# N-CW7_UserInterface.net
KiCad netlist of a schematic drawn in Altium Designer
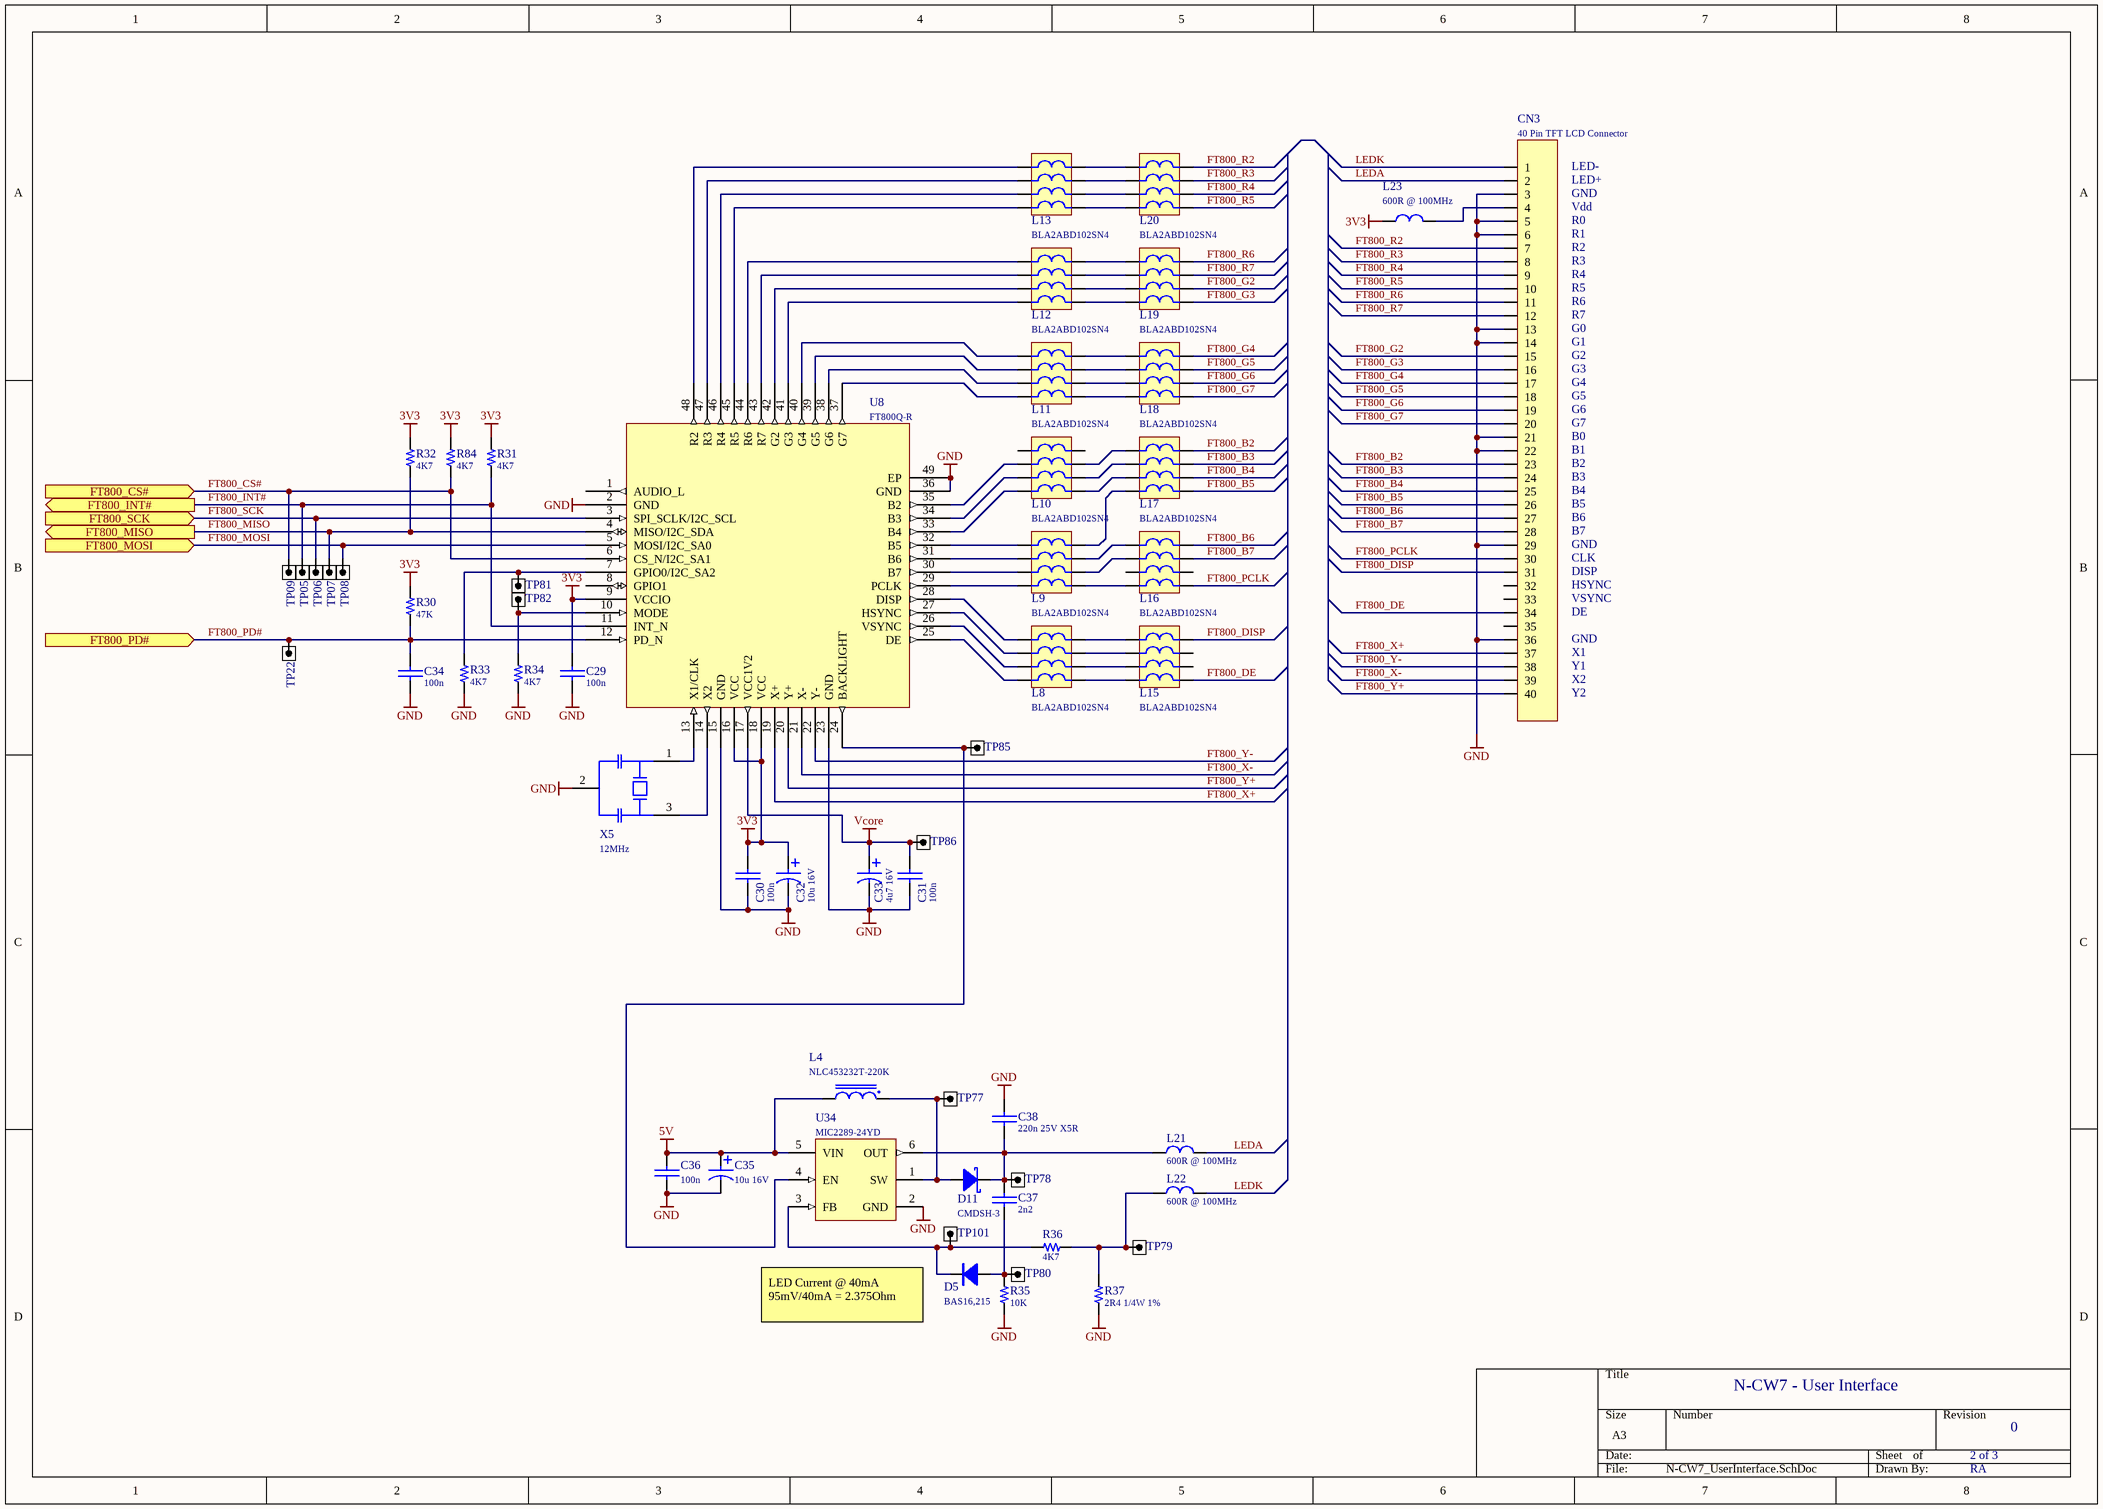
[diagram p0: N-CW7_UserInterface.SchDoc]

(export (version "E")
  (design (tool "Eeschema 10.0.6"))
  (components
    (comp (ref "C29")
      (value "100n")
      (footprint "TDK_0603_T0.80:CAPC1608X08N")
      (description "CAP CER 0.1UF 50V X7R 0603")
      (fields
        (field (name "MANUFACTURER") "TDK")
        (field (name "MANUFACTURER PART NUMBER") "C1608X7R1H104K080AA")
      )
      (libsource (lib "PassiveComponents_Capacitors_Ceramic") (part "TDK_0603_T0.80"))
    )
    (comp (ref "C30")
      (value "100n")
      (footprint "TDK_0603_T0.80:CAPC1608X08N")
      (description "CAP CER 0.1UF 50V X7R 0603")
      (fields
        (field (name "MANUFACTURER") "TDK")
        (field (name "MANUFACTURER PART NUMBER") "C1608X7R1H104K080AA")
      )
      (libsource (lib "PassiveComponents_Capacitors_Ceramic") (part "TDK_0603_T0.80"))
    )
    (comp (ref "C31")
      (value "100n")
      (footprint "TDK_0603_T0.80:CAPC1608X08N")
      (description "CAP CER 0.1UF 50V X7R 0603")
      (fields
        (field (name "MANUFACTURER") "TDK")
        (field (name "MANUFACTURER PART NUMBER") "C1608X7R1H104K080AA")
      )
      (libsource (lib "PassiveComponents_Capacitors_Ceramic") (part "TDK_0603_T0.80"))
    )
    (comp (ref "C32")
      (value "10u 16V")
      (footprint "KEMET_T494B/3528-21:CAPMP3528X19N")
      (description "CAP TANT 10UF 10% 16V 1411")
      (fields
        (field (name "MANUFACTURER") "KEMET")
        (field (name "MANUFACTURER PART NUMBER") "T494B106K016AT")
      )
      (libsource (lib "PassiveComponents_Capacitors_Tantalum") (part "KEMET_T494B/EIA3528-21"))
    )
    (comp (ref "C33")
      (value "4u7 16V")
      (footprint "KEMET_T494A/3216-18:CAPCP3216X16N")
      (description "CAP TANT 4.7UF 10% 16V 1206")
      (fields
        (field (name "MANUFACTURER") "KEMET")
        (field (name "MANUFACTURER PART NUMBER") "T494A475K016AT")
      )
      (libsource (lib "PassiveComponents_Capacitors_Tantalum") (part "KEMET_T494A/EIA3216-18"))
    )
    (comp (ref "C34")
      (value "100n")
      (footprint "TDK_0603_T0.80:CAPC1608X08N")
      (description "CAP CER 0.1UF 50V X7R 0603")
      (fields
        (field (name "MANUFACTURER") "TDK")
        (field (name "MANUFACTURER PART NUMBER") "C1608X7R1H104K080AA")
      )
      (libsource (lib "PassiveComponents_Capacitors_Ceramic") (part "TDK_0603_T0.80"))
    )
    (comp (ref "C35")
      (value "10u 16V")
      (footprint "KEMET_T494B/3528-21:CAPMP3528X19N")
      (description "CAP TANT 10UF 10% 16V 1411")
      (fields
        (field (name "MANUFACTURER") "KEMET")
        (field (name "MANUFACTURER PART NUMBER") "T494B106K016AT")
      )
      (libsource (lib "PassiveComponents_Capacitors_Tantalum") (part "KEMET_T494B/EIA3528-21"))
    )
    (comp (ref "C36")
      (value "100n")
      (footprint "TDK_0603_T0.80:CAPC1608X08N")
      (description "CAP CER 0.1UF 50V X7R 0603")
      (fields
        (field (name "MANUFACTURER") "TDK")
        (field (name "MANUFACTURER PART NUMBER") "C1608X7R1H104K080AA")
      )
      (libsource (lib "PassiveComponents_Capacitors_Ceramic") (part "TDK_0603_T0.80"))
    )
    (comp (ref "C37")
      (value "2n2")
      (footprint "TDK_0603_T0.80:CAPC1608X08N")
      (description "CAP CER 2200PF 50V X7R 0603")
      (fields
        (field (name "MANUFACTURER") "TDK")
        (field (name "MANUFACTURER PART NUMBER") "C1608X7R1H222K080AE")
      )
      (libsource (lib "PassiveComponents_Capacitors_Ceramic") (part "TDK_0603_T0.80"))
    )
    (comp (ref "C38")
      (value "220n 25V X5R")
      (footprint "AVX_0805_T1.40:CAPC2012X14N")
      (description "CAP CER 220n 25V X5R 0805")
      (libsource (lib "PassiveComponents_Capacitors_Ceramic") (part "AVX_0805_T1.40"))
    )
    (comp (ref "CN3")
      (value "40 Pin TFT LCD Connector")
      (footprint "FCI_62684-402100ALF")
      (description "CONN FPC TOP 40POS 0.5MM R/A")
      (fields
        (field (name "MANUFACTURER") "Amphenol ICC / FCI")
        (field (name "MANUFACTURER PART NUMBER") "62684-402100ALF")
      )
      (libsource (lib "Connectors") (part "FCI_62684-402100ALF"))
    )
    (comp (ref "D5")
      (value "BAS16,215")
      (footprint "NEXPERIA_BAS16,215_SOT_23:SOT95P230X110-3N")
      (description "DIODE GP 100V 215MA SOT23")
      (fields (field (name "MANUFACTURER") "Nexperia"))
      (libsource (lib "DiscreteSemiconductors_Diodes_Rectifier") (part "NEXPERIA_BAS16,215_SOT23"))
    )
    (comp (ref "D11")
      (value "CMDSH-3")
      (footprint "CSEMI_CMDSH-3_SOD323")
      (description "DIODE SCHOTTKY 30V 100MA SOD323")
      (fields
        (field (name "MANUFACTURER") "Central Semiconductor")
        (field (name "MANUFACTURER PART NUMBER") "CMDSH-3 TR PBFREE")
      )
      (libsource (lib "DiscreteSemiconductors_Diodes_Rectifier") (part "CSEMI_CMDSH-3_SOD323"))
    )
    (comp (ref "L4")
      (value "NLC453232T-220K")
      (footprint "TDK_NLC453232T-220K")
      (description "22uH 10%")
      (fields
        (field (name "MANUFACTURER") "TDK")
        (field (name "MANUFACTURER PART NUMBER") "NLC453232T-220K-PF")
      )
      (libsource (lib "PassiveComponents_Inductors") (part "TDK_NLC453232T-220K"))
    )
    (comp (ref "L8")
      (value "BLA2ABD102SN4")
      (footprint "MURATA_BLA2ABD102SN4_0804:CAF-50P200X100-8N")
      (description "Ferrite Beads 1000 OHM 25%")
      (fields
        (field (name "MANUFACTURER") "Murata")
        (field (name "MANUFACTURER PART NUMBER") "BLA2ABD102SN4B")
      )
      (libsource (lib "PassiveComponents_Inductors") (part "MURATA_BLA2ABD102SN4_0804"))
    )
    (comp (ref "L9")
      (value "BLA2ABD102SN4")
      (footprint "MURATA_BLA2ABD102SN4_0804:CAF-50P200X100-8N")
      (description "Ferrite Beads 1000 OHM 25%")
      (fields
        (field (name "MANUFACTURER") "Murata")
        (field (name "MANUFACTURER PART NUMBER") "BLA2ABD102SN4B")
      )
      (libsource (lib "PassiveComponents_Inductors") (part "MURATA_BLA2ABD102SN4_0804"))
    )
    (comp (ref "L10")
      (value "BLA2ABD102SN4")
      (footprint "MURATA_BLA2ABD102SN4_0804:CAF-50P200X100-8N")
      (description "Ferrite Beads 1000 OHM 25%")
      (fields
        (field (name "MANUFACTURER") "Murata")
        (field (name "MANUFACTURER PART NUMBER") "BLA2ABD102SN4B")
      )
      (libsource (lib "PassiveComponents_Inductors") (part "MURATA_BLA2ABD102SN4_0804"))
    )
    (comp (ref "L11")
      (value "BLA2ABD102SN4")
      (footprint "MURATA_BLA2ABD102SN4_0804:CAF-50P200X100-8N")
      (description "Ferrite Beads 1000 OHM 25%")
      (fields
        (field (name "MANUFACTURER") "Murata")
        (field (name "MANUFACTURER PART NUMBER") "BLA2ABD102SN4B")
      )
      (libsource (lib "PassiveComponents_Inductors") (part "MURATA_BLA2ABD102SN4_0804"))
    )
    (comp (ref "L12")
      (value "BLA2ABD102SN4")
      (footprint "MURATA_BLA2ABD102SN4_0804:CAF-50P200X100-8N")
      (description "Ferrite Beads 1000 OHM 25%")
      (fields
        (field (name "MANUFACTURER") "Murata")
        (field (name "MANUFACTURER PART NUMBER") "BLA2ABD102SN4B")
      )
      (libsource (lib "PassiveComponents_Inductors") (part "MURATA_BLA2ABD102SN4_0804"))
    )
    (comp (ref "L13")
      (value "BLA2ABD102SN4")
      (footprint "MURATA_BLA2ABD102SN4_0804:CAF-50P200X100-8N")
      (description "Ferrite Beads 1000 OHM 25%")
      (fields
        (field (name "MANUFACTURER") "Murata")
        (field (name "MANUFACTURER PART NUMBER") "BLA2ABD102SN4B")
      )
      (libsource (lib "PassiveComponents_Inductors") (part "MURATA_BLA2ABD102SN4_0804"))
    )
    (comp (ref "L15")
      (value "BLA2ABD102SN4")
      (footprint "MURATA_BLA2ABD102SN4_0804:CAF-50P200X100-8N")
      (description "Ferrite Beads 1000 OHM 25%")
      (fields
        (field (name "MANUFACTURER") "Murata")
        (field (name "MANUFACTURER PART NUMBER") "BLA2ABD102SN4B")
      )
      (libsource (lib "PassiveComponents_Inductors") (part "MURATA_BLA2ABD102SN4_0804"))
    )
    (comp (ref "L16")
      (value "BLA2ABD102SN4")
      (footprint "MURATA_BLA2ABD102SN4_0804:CAF-50P200X100-8N")
      (description "Ferrite Beads 1000 OHM 25%")
      (fields
        (field (name "MANUFACTURER") "Murata")
        (field (name "MANUFACTURER PART NUMBER") "BLA2ABD102SN4B")
      )
      (libsource (lib "PassiveComponents_Inductors") (part "MURATA_BLA2ABD102SN4_0804"))
    )
    (comp (ref "L17")
      (value "BLA2ABD102SN4")
      (footprint "MURATA_BLA2ABD102SN4_0804:CAF-50P200X100-8N")
      (description "Ferrite Beads 1000 OHM 25%")
      (fields
        (field (name "MANUFACTURER") "Murata")
        (field (name "MANUFACTURER PART NUMBER") "BLA2ABD102SN4B")
      )
      (libsource (lib "PassiveComponents_Inductors") (part "MURATA_BLA2ABD102SN4_0804"))
    )
    (comp (ref "L18")
      (value "BLA2ABD102SN4")
      (footprint "MURATA_BLA2ABD102SN4_0804:CAF-50P200X100-8N")
      (description "Ferrite Beads 1000 OHM 25%")
      (fields
        (field (name "MANUFACTURER") "Murata")
        (field (name "MANUFACTURER PART NUMBER") "BLA2ABD102SN4B")
      )
      (libsource (lib "PassiveComponents_Inductors") (part "MURATA_BLA2ABD102SN4_0804"))
    )
    (comp (ref "L19")
      (value "BLA2ABD102SN4")
      (footprint "MURATA_BLA2ABD102SN4_0804:CAF-50P200X100-8N")
      (description "Ferrite Beads 1000 OHM 25%")
      (fields
        (field (name "MANUFACTURER") "Murata")
        (field (name "MANUFACTURER PART NUMBER") "BLA2ABD102SN4B")
      )
      (libsource (lib "PassiveComponents_Inductors") (part "MURATA_BLA2ABD102SN4_0804"))
    )
    (comp (ref "L20")
      (value "BLA2ABD102SN4")
      (footprint "MURATA_BLA2ABD102SN4_0804:CAF-50P200X100-8N")
      (description "Ferrite Beads 1000 OHM 25%")
      (fields
        (field (name "MANUFACTURER") "Murata")
        (field (name "MANUFACTURER PART NUMBER") "BLA2ABD102SN4B")
      )
      (libsource (lib "PassiveComponents_Inductors") (part "MURATA_BLA2ABD102SN4_0804"))
    )
    (comp (ref "L21")
      (value "600R @ 100MHz")
      (footprint "LAIRD_MI0805K601R-10:INDC2012X09N")
      (description "FERRITE BEAD 600 OHM 0805 1LN")
      (fields
        (field (name "MANUFACTURER") "Laird")
        (field (name "MANUFACTURER PART NUMBER") "MI0805K601R-10")
      )
      (libsource (lib "PassiveComponents_Inductors") (part "LAIRD_MI0805K601R-10"))
    )
    (comp (ref "L22")
      (value "600R @ 100MHz")
      (footprint "LAIRD_MI0805K601R-10:INDC2012X09N")
      (description "FERRITE BEAD 600 OHM 0805 1LN")
      (fields
        (field (name "MANUFACTURER") "Laird")
        (field (name "MANUFACTURER PART NUMBER") "MI0805K601R-10")
      )
      (libsource (lib "PassiveComponents_Inductors") (part "LAIRD_MI0805K601R-10"))
    )
    (comp (ref "L23")
      (value "600R @ 100MHz")
      (footprint "LAIRD_MI0805K601R-10:INDC2012X09N")
      (description "FERRITE BEAD 600 OHM 0805 1LN")
      (fields
        (field (name "MANUFACTURER") "Laird")
        (field (name "MANUFACTURER PART NUMBER") "MI0805K601R-10")
      )
      (libsource (lib "PassiveComponents_Inductors") (part "LAIRD_MI0805K601R-10"))
    )
    (comp (ref "R30")
      (value "47K")
      (footprint "YAGEO_0603_T0.55:RESC1608X06N")
      (description "RES 47K OHM 1% 1/10W 0603")
      (fields
        (field (name "MANUFACTURER") "Yageo")
        (field (name "MANUFACTURER PART NUMBER") "RC0603FR-0747KL")
      )
      (libsource (lib "PassiveComponents_Resistors_ChipSMD") (part "YAGEO_0603_T0.55"))
    )
    (comp (ref "R31")
      (value "4K7")
      (footprint "YAGEO_0603_T0.55:RESC1608X06N")
      (description "RES 4.7K OHM 1% 1/10W 0603")
      (fields
        (field (name "MANUFACTURER") "Yageo")
        (field (name "MANUFACTURER PART NUMBER") "RC0603FR-074K7L")
      )
      (libsource (lib "PassiveComponents_Resistors_ChipSMD") (part "YAGEO_0603_T0.55"))
    )
    (comp (ref "R32")
      (value "4K7")
      (footprint "YAGEO_0603_T0.55:RESC1608X06N")
      (description "RES 4.7K OHM 1% 1/10W 0603")
      (fields
        (field (name "MANUFACTURER") "Yageo")
        (field (name "MANUFACTURER PART NUMBER") "RC0603FR-074K7L")
      )
      (libsource (lib "PassiveComponents_Resistors_ChipSMD") (part "YAGEO_0603_T0.55"))
    )
    (comp (ref "R33")
      (value "4K7")
      (footprint "YAGEO_0603_T0.55:RESC1608X06N")
      (description "RES 4.7K OHM 1% 1/10W 0603")
      (fields
        (field (name "MANUFACTURER") "Yageo")
        (field (name "MANUFACTURER PART NUMBER") "RC0603FR-074K7L")
      )
      (libsource (lib "PassiveComponents_Resistors_ChipSMD") (part "YAGEO_0603_T0.55"))
    )
    (comp (ref "R34")
      (value "4K7")
      (footprint "YAGEO_0603_T0.55:RESC1608X06N")
      (description "RES 4.7K OHM 1% 1/10W 0603")
      (fields
        (field (name "MANUFACTURER") "Yageo")
        (field (name "MANUFACTURER PART NUMBER") "RC0603FR-074K7L")
      )
      (libsource (lib "PassiveComponents_Resistors_ChipSMD") (part "YAGEO_0603_T0.55"))
    )
    (comp (ref "R35")
      (value "10K")
      (footprint "YAGEO_0603_T0.55:RESC1608X06N")
      (description "RES 10K OHM 1% 1/10W 0603")
      (fields
        (field (name "MANUFACTURER") "Yageo")
        (field (name "MANUFACTURER PART NUMBER") "RC0603FR-0710KL")
      )
      (libsource (lib "PassiveComponents_Resistors_ChipSMD") (part "YAGEO_0603_T0.55"))
    )
    (comp (ref "R36")
      (value "4K7")
      (footprint "YAGEO_0603_T0.55:RESC1608X06N")
      (description "RES 4.7K OHM 1% 1/10W 0603")
      (fields
        (field (name "MANUFACTURER") "Yageo")
        (field (name "MANUFACTURER PART NUMBER") "RC0603FR-074K7L")
      )
      (libsource (lib "PassiveComponents_Resistors_ChipSMD") (part "YAGEO_0603_T0.55"))
    )
    (comp (ref "R37")
      (value "2R4 1/4W 1%")
      (footprint "PANASONIC_ERJ-3B:RESC1608X04N")
      (description "RES SMD 2.4 OHM 1% 1/4W 0603")
      (fields
        (field (name "MANUFACTURER") "Panasonic")
        (field (name "MANUFACTURER PART NUMBER") "ERJ-3BQF2R4V")
      )
      (libsource (lib "PassiveComponents_Resistors_ChipSMD") (part "PANASONIC_ERJ-3B"))
    )
    (comp (ref "R84")
      (value "4K7")
      (footprint "YAGEO_0603_T0.55:RESC1608X06N")
      (description "RES 4.7K OHM 1% 1/10W 0603")
      (fields
        (field (name "MANUFACTURER") "Yageo")
        (field (name "MANUFACTURER PART NUMBER") "RC0603FR-074K7L")
      )
      (libsource (lib "PassiveComponents_Resistors_ChipSMD") (part "YAGEO_0603_T0.55"))
    )
    (comp (ref "TP05")
      (value "TESTPOINT_OCTAGONAL")
      (footprint "TESTPOINT_OCTAGONAL")
      (libsource (lib "") (part "TESTPOINT_OCTAGONAL_1"))
    )
    (comp (ref "TP06")
      (value "TESTPOINT_OCTAGONAL")
      (footprint "TESTPOINT_OCTAGONAL")
      (libsource (lib "") (part "TESTPOINT_OCTAGONAL_1"))
    )
    (comp (ref "TP07")
      (value "TESTPOINT_OCTAGONAL")
      (footprint "TESTPOINT_OCTAGONAL")
      (libsource (lib "") (part "TESTPOINT_OCTAGONAL_1"))
    )
    (comp (ref "TP08")
      (value "TESTPOINT_OCTAGONAL")
      (footprint "TESTPOINT_OCTAGONAL")
      (libsource (lib "") (part "TESTPOINT_OCTAGONAL_1"))
    )
    (comp (ref "TP09")
      (value "TESTPOINT_OCTAGONAL")
      (footprint "TESTPOINT_OCTAGONAL")
      (libsource (lib "") (part "TESTPOINT_OCTAGONAL_1"))
    )
    (comp (ref "TP22")
      (value "TESTPOINT_OCTAGONAL")
      (footprint "TESTPOINT_OCTAGONAL")
      (libsource (lib "") (part "TESTPOINT_OCTAGONAL_1"))
    )
    (comp (ref "TP77")
      (value "TESTPOINT_OCTAGONAL")
      (footprint "TESTPOINT_OCTAGONAL")
      (libsource (lib "Miscellaneous") (part "TESTPOINT_OCTAGONAL"))
    )
    (comp (ref "TP78")
      (value "TESTPOINT_OCTAGONAL")
      (footprint "TESTPOINT_OCTAGONAL")
      (libsource (lib "Miscellaneous") (part "TESTPOINT_OCTAGONAL"))
    )
    (comp (ref "TP79")
      (value "TESTPOINT_OCTAGONAL")
      (footprint "TESTPOINT_OCTAGONAL")
      (libsource (lib "Miscellaneous") (part "TESTPOINT_OCTAGONAL"))
    )
    (comp (ref "TP80")
      (value "TESTPOINT_OCTAGONAL")
      (footprint "TESTPOINT_OCTAGONAL")
      (libsource (lib "Miscellaneous") (part "TESTPOINT_OCTAGONAL"))
    )
    (comp (ref "TP81")
      (value "TESTPOINT_OCTAGONAL")
      (footprint "TESTPOINT_OCTAGONAL")
      (libsource (lib "") (part "TESTPOINT_OCTAGONAL_1"))
    )
    (comp (ref "TP82")
      (value "TESTPOINT_OCTAGONAL")
      (footprint "TESTPOINT_OCTAGONAL")
      (libsource (lib "") (part "TESTPOINT_OCTAGONAL_2"))
    )
    (comp (ref "TP85")
      (value "TESTPOINT_OCTAGONAL")
      (footprint "TESTPOINT_OCTAGONAL")
      (libsource (lib "Miscellaneous") (part "TESTPOINT_OCTAGONAL"))
    )
    (comp (ref "TP86")
      (value "TESTPOINT_OCTAGONAL")
      (footprint "TESTPOINT_OCTAGONAL")
      (libsource (lib "Miscellaneous") (part "TESTPOINT_OCTAGONAL"))
    )
    (comp (ref "TP101")
      (value "TESTPOINT_OCTAGONAL")
      (footprint "TESTPOINT_OCTAGONAL")
      (libsource (lib "") (part "TESTPOINT_OCTAGONAL_2"))
    )
    (comp (ref "U8")
      (value "FT800Q-R")
      (footprint "BRIDGETEK_FT800Q-R_VQFN48:QFN50P700X700X90_HS-49N")
      (description "IC VIDEO CONTROLLER 48VQFN")
      (fields (field (name "MANUFACTURER") "Bridgetek"))
      (libsource (lib "IntegratedCircuits_Embedded_Peripherals") (part "BRIDGETEK_FT800Q-R_VQFN48"))
    )
    (comp (ref "U34")
      (value "MIC2289-24YD")
      (footprint "MICREL_MIC2289-24YD_SOT236:SOT95P280X100-6N")
      (description "IC LED DRVR RGLTR PWM TSOT23-6")
      (fields
        (field (name "MANUFACTURER") "Microchip")
        (field (name "MANUFACTURER PART NUMBER") "MIC2289-24YD6-TR")
      )
      (libsource (lib "IntegratedCircuits_Power_VoltageRegsSwitchMode") (part "MICREL_MIC2289-24YD_SOT236"))
    )
    (comp (ref "X5")
      (value "12MHz")
      (footprint "MURATA_CSTNE12M0G520000R0")
      (description "CERAMIC RES 12.0000MHZ 10PF SMD")
      (fields
        (field (name "MANUFACTURER") "Murata")
        (field (name "MANUFACTURER PART NUMBER") "CSTNE12M0G520000R0")
      )
      (libsource (lib "PassiveComponents_Oscillators_Resonators") (part "MURATA_CSTNE12M0G520000R0"))
    )
  )
  (nets
    (net (code "1") (name "/FT800_B2") (class "Default")
      (node (ref "CN3") (pin "23") (pinfunction "23_23") (pintype "passive"))
      (node (ref "L17") (pin "8") (pinfunction "8_8") (pintype "passive"))
    )
    (net (code "2") (name "/FT800_B3") (class "Default")
      (node (ref "CN3") (pin "24") (pinfunction "24_24") (pintype "passive"))
      (node (ref "L17") (pin "7") (pinfunction "7_7") (pintype "passive"))
    )
    (net (code "3") (name "/FT800_B4") (class "Default")
      (node (ref "CN3") (pin "25") (pinfunction "25_25") (pintype "passive"))
      (node (ref "L17") (pin "6") (pinfunction "6_6") (pintype "passive"))
    )
    (net (code "4") (name "/FT800_B5") (class "Default")
      (node (ref "CN3") (pin "26") (pinfunction "26_26") (pintype "passive"))
      (node (ref "L17") (pin "5") (pinfunction "5_5") (pintype "passive"))
    )
    (net (code "5") (name "/FT800_B6") (class "Default")
      (node (ref "CN3") (pin "27") (pinfunction "27_27") (pintype "passive"))
      (node (ref "L16") (pin "8") (pinfunction "8_8") (pintype "passive"))
    )
    (net (code "6") (name "/FT800_B7") (class "Default")
      (node (ref "CN3") (pin "28") (pinfunction "28_28") (pintype "passive"))
      (node (ref "L16") (pin "7") (pinfunction "7_7") (pintype "passive"))
    )
    (net (code "7") (name "/FT800_CS#") (class "Default")
      (node (ref "R84") (pin "2") (pinfunction "2_2") (pintype "passive"))
      (node (ref "TP09") (pin "1") (pinfunction "1_1") (pintype "passive"))
      (node (ref "U8") (pin "6") (pinfunction "CS_N/I2C_SA1_6") (pintype "input"))
    )
    (net (code "8") (name "/FT800_DE") (class "Default")
      (node (ref "CN3") (pin "34") (pinfunction "34_34") (pintype "passive"))
      (node (ref "L15") (pin "5") (pinfunction "5_5") (pintype "passive"))
    )
    (net (code "9") (name "/FT800_DISP") (class "Default")
      (node (ref "CN3") (pin "31") (pinfunction "31_31") (pintype "passive"))
      (node (ref "L15") (pin "8") (pinfunction "8_8") (pintype "passive"))
    )
    (net (code "10") (name "/FT800_G2") (class "Default")
      (node (ref "CN3") (pin "15") (pinfunction "15_15") (pintype "passive"))
      (node (ref "L19") (pin "6") (pinfunction "6_6") (pintype "passive"))
    )
    (net (code "11") (name "/FT800_G3") (class "Default")
      (node (ref "CN3") (pin "16") (pinfunction "16_16") (pintype "passive"))
      (node (ref "L19") (pin "5") (pinfunction "5_5") (pintype "passive"))
    )
    (net (code "12") (name "/FT800_G4") (class "Default")
      (node (ref "CN3") (pin "17") (pinfunction "17_17") (pintype "passive"))
      (node (ref "L18") (pin "8") (pinfunction "8_8") (pintype "passive"))
    )
    (net (code "13") (name "/FT800_G5") (class "Default")
      (node (ref "CN3") (pin "18") (pinfunction "18_18") (pintype "passive"))
      (node (ref "L18") (pin "7") (pinfunction "7_7") (pintype "passive"))
    )
    (net (code "14") (name "/FT800_G6") (class "Default")
      (node (ref "CN3") (pin "19") (pinfunction "19_19") (pintype "passive"))
      (node (ref "L18") (pin "6") (pinfunction "6_6") (pintype "passive"))
    )
    (net (code "15") (name "/FT800_G7") (class "Default")
      (node (ref "CN3") (pin "20") (pinfunction "20_20") (pintype "passive"))
      (node (ref "L18") (pin "5") (pinfunction "5_5") (pintype "passive"))
    )
    (net (code "16") (name "/FT800_INT#") (class "Default")
      (node (ref "R31") (pin "2") (pinfunction "2_2") (pintype "passive"))
      (node (ref "TP05") (pin "1") (pinfunction "1_1") (pintype "passive"))
      (node (ref "U8") (pin "11") (pinfunction "INT_N_11") (pintype "open_collector"))
    )
    (net (code "17") (name "/FT800_MISO") (class "Default")
      (node (ref "R32") (pin "2") (pinfunction "2_2") (pintype "passive"))
      (node (ref "TP07") (pin "1") (pinfunction "1_1") (pintype "passive"))
      (node (ref "U8") (pin "4") (pinfunction "MISO/I2C_SDA_4") (pintype "bidirectional"))
    )
    (net (code "18") (name "/FT800_MOSI") (class "Default")
      (node (ref "TP08") (pin "1") (pinfunction "1_1") (pintype "passive"))
      (node (ref "U8") (pin "5") (pinfunction "MOSI/I2C_SA0_5") (pintype "input"))
    )
    (net (code "19") (name "/FT800_PCLK") (class "Default")
      (node (ref "CN3") (pin "30") (pinfunction "30_30") (pintype "passive"))
      (node (ref "L16") (pin "5") (pinfunction "5_5") (pintype "passive"))
    )
    (net (code "20") (name "/FT800_PD#") (class "Default")
      (node (ref "C34") (pin "2") (pinfunction "2_2") (pintype "passive"))
      (node (ref "R30") (pin "1") (pinfunction "1_1") (pintype "passive"))
      (node (ref "TP22") (pin "1") (pinfunction "1_1") (pintype "passive"))
      (node (ref "U8") (pin "12") (pinfunction "PD_N_12") (pintype "input"))
    )
    (net (code "21") (name "/FT800_R2") (class "Default")
      (node (ref "CN3") (pin "7") (pinfunction "7_7") (pintype "passive"))
      (node (ref "L20") (pin "8") (pinfunction "8_8") (pintype "passive"))
    )
    (net (code "22") (name "/FT800_R3") (class "Default")
      (node (ref "CN3") (pin "8") (pinfunction "8_8") (pintype "passive"))
      (node (ref "L20") (pin "7") (pinfunction "7_7") (pintype "passive"))
    )
    (net (code "23") (name "/FT800_R4") (class "Default")
      (node (ref "CN3") (pin "9") (pinfunction "9_9") (pintype "passive"))
      (node (ref "L20") (pin "6") (pinfunction "6_6") (pintype "passive"))
    )
    (net (code "24") (name "/FT800_R5") (class "Default")
      (node (ref "CN3") (pin "10") (pinfunction "10_10") (pintype "passive"))
      (node (ref "L20") (pin "5") (pinfunction "5_5") (pintype "passive"))
    )
    (net (code "25") (name "/FT800_R6") (class "Default")
      (node (ref "CN3") (pin "11") (pinfunction "11_11") (pintype "passive"))
      (node (ref "L19") (pin "8") (pinfunction "8_8") (pintype "passive"))
    )
    (net (code "26") (name "/FT800_R7") (class "Default")
      (node (ref "CN3") (pin "12") (pinfunction "12_12") (pintype "passive"))
      (node (ref "L19") (pin "7") (pinfunction "7_7") (pintype "passive"))
    )
    (net (code "27") (name "/FT800_SCK") (class "Default")
      (node (ref "TP06") (pin "1") (pinfunction "1_1") (pintype "passive"))
      (node (ref "U8") (pin "3") (pinfunction "SPI_SCLK/I2C_SCL_3") (pintype "input"))
    )
    (net (code "28") (name "/FT800_X+") (class "Default")
      (node (ref "CN3") (pin "37") (pinfunction "37_37") (pintype "passive"))
      (node (ref "U8") (pin "19") (pinfunction "X+_19") (pintype "passive"))
    )
    (net (code "29") (name "/FT800_X-") (class "Default")
      (node (ref "CN3") (pin "39") (pinfunction "39_39") (pintype "passive"))
      (node (ref "U8") (pin "21") (pinfunction "X-_21") (pintype "passive"))
    )
    (net (code "30") (name "/FT800_Y+") (class "Default")
      (node (ref "CN3") (pin "40") (pinfunction "40_40") (pintype "passive"))
      (node (ref "U8") (pin "20") (pinfunction "Y+_20") (pintype "passive"))
    )
    (net (code "31") (name "/FT800_Y-") (class "Default")
      (node (ref "CN3") (pin "38") (pinfunction "38_38") (pintype "passive"))
      (node (ref "U8") (pin "22") (pinfunction "Y-_22") (pintype "passive"))
    )
    (net (code "32") (name "/LEDA") (class "Default")
      (node (ref "CN3") (pin "2") (pinfunction "2_2") (pintype "power_in"))
      (node (ref "L21") (pin "2") (pinfunction "2_2") (pintype "passive"))
    )
    (net (code "33") (name "/LEDK") (class "Default")
      (node (ref "CN3") (pin "1") (pinfunction "1_1") (pintype "power_in"))
      (node (ref "L22") (pin "2") (pinfunction "2_2") (pintype "passive"))
    )
    (net (code "34") (name "3V3") (class "Default")
      (node (ref "C29") (pin "2") (pinfunction "2_2") (pintype "passive"))
      (node (ref "C30") (pin "2") (pinfunction "2_2") (pintype "passive"))
      (node (ref "C32") (pin "1") (pinfunction "1_1") (pintype "passive"))
      (node (ref "L23") (pin "1") (pinfunction "1_1") (pintype "passive"))
      (node (ref "R30") (pin "2") (pinfunction "2_2") (pintype "passive"))
      (node (ref "R31") (pin "1") (pinfunction "1_1") (pintype "passive"))
      (node (ref "R32") (pin "1") (pinfunction "1_1") (pintype "passive"))
      (node (ref "R84") (pin "1") (pinfunction "1_1") (pintype "passive"))
      (node (ref "U8") (pin "16") (pinfunction "VCC_16") (pintype "power_in"))
      (node (ref "U8") (pin "18") (pinfunction "VCC_18") (pintype "power_in"))
      (node (ref "U8") (pin "9") (pinfunction "VCCIO_9") (pintype "power_in"))
    )
    (net (code "35") (name "5V") (class "Default")
      (node (ref "C35") (pin "1") (pinfunction "1_1") (pintype "passive"))
      (node (ref "C36") (pin "1") (pinfunction "1_1") (pintype "passive"))
      (node (ref "L4") (pin "2") (pinfunction "2_2") (pintype "passive"))
      (node (ref "U34") (pin "5") (pinfunction "VIN_5") (pintype "power_in"))
    )
    (net (code "36") (name "GND") (class "Default")
      (node (ref "C29") (pin "1") (pinfunction "1_1") (pintype "passive"))
      (node (ref "C30") (pin "1") (pinfunction "1_1") (pintype "passive"))
      (node (ref "C31") (pin "1") (pinfunction "1_1") (pintype "passive"))
      (node (ref "C32") (pin "2") (pinfunction "2_2") (pintype "passive"))
      (node (ref "C33") (pin "2") (pinfunction "2_2") (pintype "passive"))
      (node (ref "C34") (pin "1") (pinfunction "1_1") (pintype "passive"))
      (node (ref "C35") (pin "2") (pinfunction "2_2") (pintype "passive"))
      (node (ref "C36") (pin "2") (pinfunction "2_2") (pintype "passive"))
      (node (ref "C38") (pin "2") (pinfunction "2_2") (pintype "passive"))
      (node (ref "CN3") (pin "13") (pinfunction "13_13") (pintype "passive"))
      (node (ref "CN3") (pin "14") (pinfunction "14_14") (pintype "passive"))
      (node (ref "CN3") (pin "21") (pinfunction "21_21") (pintype "passive"))
      (node (ref "CN3") (pin "22") (pinfunction "22_22") (pintype "passive"))
      (node (ref "CN3") (pin "29") (pinfunction "29_29") (pintype "passive"))
      (node (ref "CN3") (pin "3") (pinfunction "3_3") (pintype "power_in"))
      (node (ref "CN3") (pin "36") (pinfunction "36_36") (pintype "passive"))
      (node (ref "CN3") (pin "5") (pinfunction "5_5") (pintype "passive"))
      (node (ref "CN3") (pin "6") (pinfunction "6_6") (pintype "passive"))
      (node (ref "R33") (pin "2") (pinfunction "2_2") (pintype "passive"))
      (node (ref "R34") (pin "2") (pinfunction "2_2") (pintype "passive"))
      (node (ref "R35") (pin "1") (pinfunction "1_1") (pintype "passive"))
      (node (ref "R37") (pin "1") (pinfunction "1_1") (pintype "passive"))
      (node (ref "U34") (pin "2") (pinfunction "GND_2") (pintype "power_in"))
      (node (ref "U8") (pin "15") (pinfunction "GND_15") (pintype "power_in"))
      (node (ref "U8") (pin "2") (pinfunction "GND_2") (pintype "power_in"))
      (node (ref "U8") (pin "23") (pinfunction "GND_23") (pintype "power_in"))
      (node (ref "U8") (pin "36") (pinfunction "GND_36") (pintype "power_in"))
      (node (ref "U8") (pin "49") (pinfunction "EP_49") (pintype "power_in"))
      (node (ref "X5") (pin "2") (pinfunction "2_2") (pintype "passive"))
    )
    (net (code "37") (name "Net-(CN3-Pad4)") (class "Default")
      (node (ref "CN3") (pin "4") (pinfunction "4_4") (pintype "power_in"))
      (node (ref "L23") (pin "2") (pinfunction "2_2") (pintype "passive"))
    )
    (net (code "38") (name "Net-(D5-A)") (class "Default")
      (node (ref "C37") (pin "1") (pinfunction "1_1") (pintype "passive"))
      (node (ref "D5") (pin "1") (pinfunction "A_1") (pintype "passive"))
      (node (ref "R35") (pin "2") (pinfunction "2_2") (pintype "passive"))
      (node (ref "TP80") (pin "1") (pinfunction "1_1") (pintype "passive"))
    )
    (net (code "39") (name "Net-(D5-K)") (class "Default")
      (node (ref "D5") (pin "3") (pinfunction "K_3") (pintype "passive"))
      (node (ref "R36") (pin "2") (pinfunction "2_2") (pintype "passive"))
      (node (ref "TP101") (pin "1") (pinfunction "1_1") (pintype "passive"))
      (node (ref "U34") (pin "3") (pinfunction "FB_3") (pintype "input"))
    )
    (net (code "40") (name "Net-(D11-A)") (class "Default")
      (node (ref "D11") (pin "2") (pinfunction "A_2") (pintype "passive"))
      (node (ref "L4") (pin "1") (pinfunction "1_1") (pintype "passive"))
      (node (ref "TP77") (pin "1") (pinfunction "1_1") (pintype "passive"))
      (node (ref "U34") (pin "1") (pinfunction "SW_1") (pintype "power_in"))
    )
    (net (code "41") (name "Net-(D11-K)") (class "Default")
      (node (ref "C37") (pin "2") (pinfunction "2_2") (pintype "passive"))
      (node (ref "C38") (pin "1") (pinfunction "1_1") (pintype "passive"))
      (node (ref "D11") (pin "1") (pinfunction "K_1") (pintype "passive"))
      (node (ref "L21") (pin "1") (pinfunction "1_1") (pintype "passive"))
      (node (ref "TP78") (pin "1") (pinfunction "1_1") (pintype "passive"))
      (node (ref "U34") (pin "6") (pinfunction "OUT_6") (pintype "output"))
    )
    (net (code "42") (name "Net-(L10-Pad5)") (class "Default")
      (node (ref "L10") (pin "5") (pinfunction "5_5") (pintype "passive"))
      (node (ref "L17") (pin "3") (pinfunction "3_3") (pintype "passive"))
    )
    (net (code "43") (name "Net-(L10-Pad6)") (class "Default")
      (node (ref "L10") (pin "6") (pinfunction "6_6") (pintype "passive"))
      (node (ref "L17") (pin "2") (pinfunction "2_2") (pintype "passive"))
    )
    (net (code "44") (name "Net-(L10-Pad7)") (class "Default")
      (node (ref "L10") (pin "7") (pinfunction "7_7") (pintype "passive"))
      (node (ref "L17") (pin "1") (pinfunction "1_1") (pintype "passive"))
    )
    (net (code "45") (name "Net-(L11-Pad5)") (class "Default")
      (node (ref "L11") (pin "5") (pinfunction "5_5") (pintype "passive"))
      (node (ref "L18") (pin "4") (pinfunction "4_4") (pintype "passive"))
    )
    (net (code "46") (name "Net-(L11-Pad6)") (class "Default")
      (node (ref "L11") (pin "6") (pinfunction "6_6") (pintype "passive"))
      (node (ref "L18") (pin "3") (pinfunction "3_3") (pintype "passive"))
    )
    (net (code "47") (name "Net-(L11-Pad7)") (class "Default")
      (node (ref "L11") (pin "7") (pinfunction "7_7") (pintype "passive"))
      (node (ref "L18") (pin "2") (pinfunction "2_2") (pintype "passive"))
    )
    (net (code "48") (name "Net-(L11-Pad8)") (class "Default")
      (node (ref "L11") (pin "8") (pinfunction "8_8") (pintype "passive"))
      (node (ref "L18") (pin "1") (pinfunction "1_1") (pintype "passive"))
    )
    (net (code "49") (name "Net-(L12-Pad5)") (class "Default")
      (node (ref "L12") (pin "5") (pinfunction "5_5") (pintype "passive"))
      (node (ref "L19") (pin "4") (pinfunction "4_4") (pintype "passive"))
    )
    (net (code "50") (name "Net-(L12-Pad6)") (class "Default")
      (node (ref "L12") (pin "6") (pinfunction "6_6") (pintype "passive"))
      (node (ref "L19") (pin "3") (pinfunction "3_3") (pintype "passive"))
    )
    (net (code "51") (name "Net-(L12-Pad7)") (class "Default")
      (node (ref "L12") (pin "7") (pinfunction "7_7") (pintype "passive"))
      (node (ref "L19") (pin "2") (pinfunction "2_2") (pintype "passive"))
    )
    (net (code "52") (name "Net-(L12-Pad8)") (class "Default")
      (node (ref "L12") (pin "8") (pinfunction "8_8") (pintype "passive"))
      (node (ref "L19") (pin "1") (pinfunction "1_1") (pintype "passive"))
    )
    (net (code "53") (name "Net-(L13-Pad5)") (class "Default")
      (node (ref "L13") (pin "5") (pinfunction "5_5") (pintype "passive"))
      (node (ref "L20") (pin "4") (pinfunction "4_4") (pintype "passive"))
    )
    (net (code "54") (name "Net-(L13-Pad6)") (class "Default")
      (node (ref "L13") (pin "6") (pinfunction "6_6") (pintype "passive"))
      (node (ref "L20") (pin "3") (pinfunction "3_3") (pintype "passive"))
    )
    (net (code "55") (name "Net-(L13-Pad7)") (class "Default")
      (node (ref "L13") (pin "7") (pinfunction "7_7") (pintype "passive"))
      (node (ref "L20") (pin "2") (pinfunction "2_2") (pintype "passive"))
    )
    (net (code "56") (name "Net-(L13-Pad8)") (class "Default")
      (node (ref "L13") (pin "8") (pinfunction "8_8") (pintype "passive"))
      (node (ref "L20") (pin "1") (pinfunction "1_1") (pintype "passive"))
    )
    (net (code "57") (name "Net-(L15-Pad1)") (class "Default")
      (node (ref "L15") (pin "1") (pinfunction "1_1") (pintype "passive"))
      (node (ref "L8") (pin "8") (pinfunction "8_8") (pintype "passive"))
    )
    (net (code "58") (name "Net-(L15-Pad2)") (class "Default")
      (node (ref "L15") (pin "2") (pinfunction "2_2") (pintype "passive"))
      (node (ref "L8") (pin "7") (pinfunction "7_7") (pintype "passive"))
    )
    (net (code "59") (name "Net-(L15-Pad3)") (class "Default")
      (node (ref "L15") (pin "3") (pinfunction "3_3") (pintype "passive"))
      (node (ref "L8") (pin "6") (pinfunction "6_6") (pintype "passive"))
    )
    (net (code "60") (name "Net-(L15-Pad4)") (class "Default")
      (node (ref "L15") (pin "4") (pinfunction "4_4") (pintype "passive"))
      (node (ref "L8") (pin "5") (pinfunction "5_5") (pintype "passive"))
    )
    (net (code "61") (name "Net-(L16-Pad1)") (class "Default")
      (node (ref "L16") (pin "1") (pinfunction "1_1") (pintype "passive"))
      (node (ref "L9") (pin "7") (pinfunction "7_7") (pintype "passive"))
    )
    (net (code "62") (name "Net-(L16-Pad2)") (class "Default")
      (node (ref "L16") (pin "2") (pinfunction "2_2") (pintype "passive"))
      (node (ref "L9") (pin "6") (pinfunction "6_6") (pintype "passive"))
    )
    (net (code "63") (name "Net-(L16-Pad4)") (class "Default")
      (node (ref "L16") (pin "4") (pinfunction "4_4") (pintype "passive"))
      (node (ref "L9") (pin "5") (pinfunction "5_5") (pintype "passive"))
    )
    (net (code "64") (name "Net-(L17-Pad4)") (class "Default")
      (node (ref "L17") (pin "4") (pinfunction "4_4") (pintype "passive"))
      (node (ref "L9") (pin "8") (pinfunction "8_8") (pintype "passive"))
    )
    (net (code "65") (name "Net-(L22-Pad1)") (class "Default")
      (node (ref "L22") (pin "1") (pinfunction "1_1") (pintype "passive"))
      (node (ref "R36") (pin "1") (pinfunction "1_1") (pintype "passive"))
      (node (ref "R37") (pin "2") (pinfunction "2_2") (pintype "passive"))
      (node (ref "TP79") (pin "1") (pinfunction "1_1") (pintype "passive"))
    )
    (net (code "66") (name "Net-(U8-B2)") (class "Default")
      (node (ref "L10") (pin "2") (pinfunction "2_2") (pintype "passive"))
      (node (ref "U8") (pin "35") (pinfunction "B2_35") (pintype "output"))
    )
    (net (code "67") (name "Net-(U8-B3)") (class "Default")
      (node (ref "L10") (pin "3") (pinfunction "3_3") (pintype "passive"))
      (node (ref "U8") (pin "34") (pinfunction "B3_34") (pintype "output"))
    )
    (net (code "68") (name "Net-(U8-B4)") (class "Default")
      (node (ref "L10") (pin "4") (pinfunction "4_4") (pintype "passive"))
      (node (ref "U8") (pin "33") (pinfunction "B4_33") (pintype "output"))
    )
    (net (code "69") (name "Net-(U8-B5)") (class "Default")
      (node (ref "L9") (pin "1") (pinfunction "1_1") (pintype "passive"))
      (node (ref "U8") (pin "32") (pinfunction "B5_32") (pintype "output"))
    )
    (net (code "70") (name "Net-(U8-B6)") (class "Default")
      (node (ref "L9") (pin "2") (pinfunction "2_2") (pintype "passive"))
      (node (ref "U8") (pin "31") (pinfunction "B6_31") (pintype "output"))
    )
    (net (code "71") (name "Net-(U8-B7)") (class "Default")
      (node (ref "L9") (pin "3") (pinfunction "3_3") (pintype "passive"))
      (node (ref "U8") (pin "30") (pinfunction "B7_30") (pintype "output"))
    )
    (net (code "72") (name "Net-(U8-DE)") (class "Default")
      (node (ref "L8") (pin "4") (pinfunction "4_4") (pintype "passive"))
      (node (ref "U8") (pin "25") (pinfunction "DE_25") (pintype "output"))
    )
    (net (code "73") (name "Net-(U8-DISP)") (class "Default")
      (node (ref "L8") (pin "1") (pinfunction "1_1") (pintype "passive"))
      (node (ref "U8") (pin "28") (pinfunction "DISP_28") (pintype "output"))
    )
    (net (code "74") (name "Net-(U8-G2)") (class "Default")
      (node (ref "L12") (pin "3") (pinfunction "3_3") (pintype "passive"))
      (node (ref "U8") (pin "42") (pinfunction "G2_42") (pintype "output"))
    )
    (net (code "75") (name "Net-(U8-G3)") (class "Default")
      (node (ref "L12") (pin "4") (pinfunction "4_4") (pintype "passive"))
      (node (ref "U8") (pin "41") (pinfunction "G3_41") (pintype "output"))
    )
    (net (code "76") (name "Net-(U8-G4)") (class "Default")
      (node (ref "L11") (pin "1") (pinfunction "1_1") (pintype "passive"))
      (node (ref "U8") (pin "40") (pinfunction "G4_40") (pintype "output"))
    )
    (net (code "77") (name "Net-(U8-G5)") (class "Default")
      (node (ref "L11") (pin "2") (pinfunction "2_2") (pintype "passive"))
      (node (ref "U8") (pin "39") (pinfunction "G5_39") (pintype "output"))
    )
    (net (code "78") (name "Net-(U8-G6)") (class "Default")
      (node (ref "L11") (pin "3") (pinfunction "3_3") (pintype "passive"))
      (node (ref "U8") (pin "38") (pinfunction "G6_38") (pintype "output"))
    )
    (net (code "79") (name "Net-(U8-G7)") (class "Default")
      (node (ref "L11") (pin "4") (pinfunction "4_4") (pintype "passive"))
      (node (ref "U8") (pin "37") (pinfunction "G7_37") (pintype "output"))
    )
    (net (code "80") (name "Net-(U8-GPIO0{slash}I2C_SA2)") (class "Default")
      (node (ref "R33") (pin "1") (pinfunction "1_1") (pintype "passive"))
      (node (ref "TP81") (pin "1") (pinfunction "1_1") (pintype "passive"))
      (node (ref "U8") (pin "7") (pinfunction "GPIO0/I2C_SA2_7") (pintype "power_in"))
    )
    (net (code "81") (name "Net-(U8-HSYNC)") (class "Default")
      (node (ref "L8") (pin "2") (pinfunction "2_2") (pintype "passive"))
      (node (ref "U8") (pin "27") (pinfunction "HSYNC_27") (pintype "output"))
    )
    (net (code "82") (name "Net-(U8-MODE)") (class "Default")
      (node (ref "R34") (pin "1") (pinfunction "1_1") (pintype "passive"))
      (node (ref "TP82") (pin "1") (pinfunction "1_1") (pintype "passive"))
      (node (ref "U8") (pin "10") (pinfunction "MODE_10") (pintype "input"))
    )
    (net (code "83") (name "Net-(U8-PCLK)") (class "Default")
      (node (ref "L9") (pin "4") (pinfunction "4_4") (pintype "passive"))
      (node (ref "U8") (pin "29") (pinfunction "PCLK_29") (pintype "output"))
    )
    (net (code "84") (name "Net-(U8-R2)") (class "Default")
      (node (ref "L13") (pin "1") (pinfunction "1_1") (pintype "passive"))
      (node (ref "U8") (pin "48") (pinfunction "R2_48") (pintype "output"))
    )
    (net (code "85") (name "Net-(U8-R3)") (class "Default")
      (node (ref "L13") (pin "2") (pinfunction "2_2") (pintype "passive"))
      (node (ref "U8") (pin "47") (pinfunction "R3_47") (pintype "output"))
    )
    (net (code "86") (name "Net-(U8-R4)") (class "Default")
      (node (ref "L13") (pin "3") (pinfunction "3_3") (pintype "passive"))
      (node (ref "U8") (pin "46") (pinfunction "R4_46") (pintype "output"))
    )
    (net (code "87") (name "Net-(U8-R5)") (class "Default")
      (node (ref "L13") (pin "4") (pinfunction "4_4") (pintype "passive"))
      (node (ref "U8") (pin "45") (pinfunction "R5_45") (pintype "output"))
    )
    (net (code "88") (name "Net-(U8-R6)") (class "Default")
      (node (ref "L12") (pin "1") (pinfunction "1_1") (pintype "passive"))
      (node (ref "U8") (pin "44") (pinfunction "R6_44") (pintype "output"))
    )
    (net (code "89") (name "Net-(U8-R7)") (class "Default")
      (node (ref "L12") (pin "2") (pinfunction "2_2") (pintype "passive"))
      (node (ref "U8") (pin "43") (pinfunction "R7_43") (pintype "output"))
    )
    (net (code "90") (name "Net-(U8-VSYNC)") (class "Default")
      (node (ref "L8") (pin "3") (pinfunction "3_3") (pintype "passive"))
      (node (ref "U8") (pin "26") (pinfunction "VSYNC_26") (pintype "output"))
    )
    (net (code "91") (name "Net-(U8-X1{slash}CLK)") (class "Default")
      (node (ref "U8") (pin "13") (pinfunction "X1/CLK_13") (pintype "input"))
      (node (ref "X5") (pin "1") (pinfunction "1_1") (pintype "passive"))
    )
    (net (code "92") (name "Net-(U8-X2)") (class "Default")
      (node (ref "U8") (pin "14") (pinfunction "X2_14") (pintype "output"))
      (node (ref "X5") (pin "3") (pinfunction "3_3") (pintype "passive"))
    )
    (net (code "93") (name "Net-(U34-EN)") (class "Default")
      (node (ref "TP85") (pin "1") (pinfunction "1_1") (pintype "passive"))
      (node (ref "U34") (pin "4") (pinfunction "EN_4") (pintype "input"))
      (node (ref "U8") (pin "24") (pinfunction "BACKLIGHT_24") (pintype "output"))
    )
    (net (code "94") (name "Vcore") (class "Default")
      (node (ref "C31") (pin "2") (pinfunction "2_2") (pintype "passive"))
      (node (ref "C33") (pin "1") (pinfunction "1_1") (pintype "passive"))
      (node (ref "TP86") (pin "1") (pinfunction "1_1") (pintype "passive"))
      (node (ref "U8") (pin "17") (pinfunction "VCC1V2_17") (pintype "output"))
    )
    (net (code "95") (name "unconnected-(CN3-Pad32)") (class "Default")
      (node (ref "CN3") (pin "32") (pinfunction "32_32") (pintype "passive"))
    )
    (net (code "96") (name "unconnected-(CN3-Pad33)") (class "Default")
      (node (ref "CN3") (pin "33") (pinfunction "33_33") (pintype "passive"))
    )
    (net (code "97") (name "unconnected-(CN3-Pad35)") (class "Default")
      (node (ref "CN3") (pin "35") (pinfunction "35_35") (pintype "passive"))
    )
    (net (code "98") (name "unconnected-(L10-Pad1)") (class "Default")
      (node (ref "L10") (pin "1") (pinfunction "1_1") (pintype "passive"))
    )
    (net (code "99") (name "unconnected-(L10-Pad8)") (class "Default")
      (node (ref "L10") (pin "8") (pinfunction "8_8") (pintype "passive"))
    )
    (net (code "100") (name "unconnected-(L15-Pad6)") (class "Default")
      (node (ref "L15") (pin "6") (pinfunction "6_6") (pintype "passive"))
    )
    (net (code "101") (name "unconnected-(L15-Pad7)") (class "Default")
      (node (ref "L15") (pin "7") (pinfunction "7_7") (pintype "passive"))
    )
    (net (code "102") (name "unconnected-(L16-Pad3)") (class "Default")
      (node (ref "L16") (pin "3") (pinfunction "3_3") (pintype "passive"))
    )
    (net (code "103") (name "unconnected-(L16-Pad6)") (class "Default")
      (node (ref "L16") (pin "6") (pinfunction "6_6") (pintype "passive"))
    )
    (net (code "104") (name "unconnected-(U8-AUDIO_L-Pad1)") (class "Default")
      (node (ref "U8") (pin "1") (pinfunction "AUDIO_L_1") (pintype "output"))
    )
    (net (code "105") (name "unconnected-(U8-GPIO1-Pad8)") (class "Default")
      (node (ref "U8") (pin "8") (pinfunction "GPIO1_8") (pintype "bidirectional"))
    )
  )
)
